# LM317-LM337.net
KiCad netlist of a schematic drawn in Altium Designer
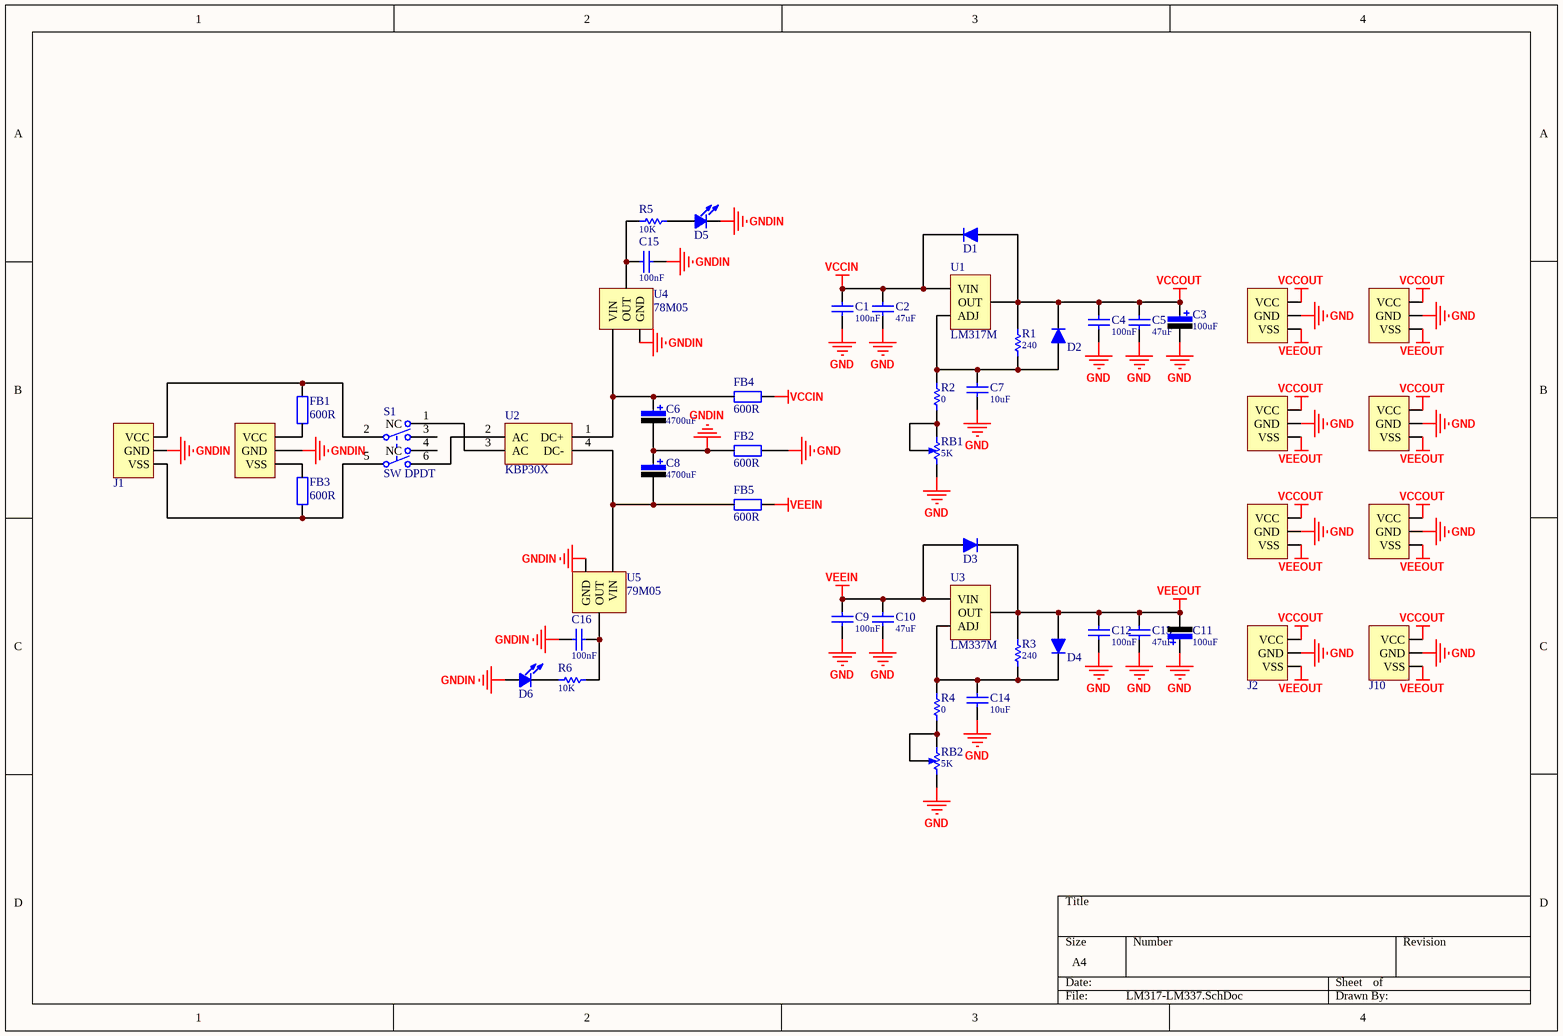
[diagram p0: LM317-LM337.SchDoc]

(export (version "E")
  (design (tool "Eeschema 10.0.6"))
  (components
    (comp (ref "C1")
      (value "100nF")
      (footprint "C0603-L")
      (description "贴片瓷片电容")
      (fields (field (name "Comment") "Cap-S"))
      (libsource (lib "CommonUsed") (part "Cap-S"))
    )
    (comp (ref "C2")
      (value "47uF")
      (footprint "C0805-L")
      (description "贴片瓷片电容")
      (fields (field (name "Comment") "Cap-S"))
      (libsource (lib "CommonUsed") (part "Cap-S"))
    )
    (comp (ref "C3")
      (value "100uF")
      (footprint "C-DIP-10")
      (description "极性直插电解电容")
      (fields (field (name "Comment") "C"))
      (libsource (lib "CommonUsed") (part "Cap-Pol-ER"))
    )
    (comp (ref "C4")
      (value "100nF")
      (footprint "C0603-L")
      (description "贴片瓷片电容")
      (fields (field (name "Comment") "Cap-S"))
      (libsource (lib "CommonUsed") (part "Cap-S"))
    )
    (comp (ref "C5")
      (value "47uF")
      (footprint "C0805-L")
      (description "贴片瓷片电容")
      (fields (field (name "Comment") "Cap-S"))
      (libsource (lib "CommonUsed") (part "Cap-S"))
    )
    (comp (ref "C6")
      (value "4700uF")
      (footprint "C-DIP-20")
      (description "极性直插电解电容")
      (fields (field (name "Comment") "C"))
      (libsource (lib "CommonUsed") (part "Cap-Pol-ER"))
    )
    (comp (ref "C7")
      (value "10uF")
      (footprint "C0603-L")
      (description "贴片瓷片电容")
      (fields (field (name "Comment") "Cap-S"))
      (libsource (lib "CommonUsed") (part "Cap-S"))
    )
    (comp (ref "C8")
      (value "4700uF")
      (footprint "C-DIP-20")
      (description "极性直插电解电容")
      (fields (field (name "Comment") "C"))
      (libsource (lib "CommonUsed") (part "Cap-Pol-ER"))
    )
    (comp (ref "C9")
      (value "100nF")
      (footprint "C0603-L")
      (description "贴片瓷片电容")
      (fields (field (name "Comment") "Cap-S"))
      (libsource (lib "CommonUsed") (part "Cap-S"))
    )
    (comp (ref "C10")
      (value "47uF")
      (footprint "C0805-L")
      (description "贴片瓷片电容")
      (fields (field (name "Comment") "Cap-S"))
      (libsource (lib "CommonUsed") (part "Cap-S"))
    )
    (comp (ref "C11")
      (value "100uF")
      (footprint "C-DIP-10")
      (description "极性直插电解电容")
      (fields (field (name "Comment") "C"))
      (libsource (lib "") (part "Cap-Pol-ER_1"))
    )
    (comp (ref "C12")
      (value "100nF")
      (footprint "C0603-L")
      (description "贴片瓷片电容")
      (fields (field (name "Comment") "Cap-S"))
      (libsource (lib "CommonUsed") (part "Cap-S"))
    )
    (comp (ref "C13")
      (value "47uF")
      (footprint "C0805-L")
      (description "贴片瓷片电容")
      (fields (field (name "Comment") "Cap-S"))
      (libsource (lib "CommonUsed") (part "Cap-S"))
    )
    (comp (ref "C14")
      (value "10uF")
      (footprint "C0603-L")
      (description "贴片瓷片电容")
      (fields (field (name "Comment") "Cap-S"))
      (libsource (lib "CommonUsed") (part "Cap-S"))
    )
    (comp (ref "C15")
      (value "100nF")
      (footprint "C0603-L")
      (description "贴片瓷片电容")
      (fields (field (name "Comment") "Cap-S"))
      (libsource (lib "CommonUsed") (part "Cap-S"))
    )
    (comp (ref "C16")
      (value "100nF")
      (footprint "C0603-L")
      (description "贴片瓷片电容")
      (fields (field (name "Comment") "Cap-S"))
      (libsource (lib "CommonUsed") (part "Cap-S"))
    )
    (comp (ref "D1")
      (value "D")
      (footprint "D-SMA")
      (description "二极管")
      (libsource (lib "CommonUsed") (part "Diode"))
    )
    (comp (ref "D2")
      (value "D")
      (footprint "D-SMA")
      (description "二极管")
      (libsource (lib "CommonUsed") (part "Diode"))
    )
    (comp (ref "D3")
      (value "D")
      (footprint "D-SMA")
      (description "二极管")
      (libsource (lib "CommonUsed") (part "Diode"))
    )
    (comp (ref "D4")
      (value "D")
      (footprint "D-SMA")
      (description "二极管")
      (libsource (lib "CommonUsed") (part "Diode"))
    )
    (comp (ref "D5")
      (value "LED")
      (footprint "Led-0805_L")
      (description "发光二极管")
      (libsource (lib "CommonUsed") (part "LED"))
    )
    (comp (ref "D6")
      (value "LED")
      (footprint "Led-0805_L")
      (description "发光二极管")
      (libsource (lib "CommonUsed") (part "LED"))
    )
    (comp (ref "FB1") (value "600R") (footprint "FB-0805") (libsource (lib "CommonUsed") (part "FB")))
    (comp (ref "FB2") (value "600R") (footprint "FB-0805") (libsource (lib "CommonUsed") (part "FB")))
    (comp (ref "FB3") (value "600R") (footprint "FB-0805") (libsource (lib "CommonUsed") (part "FB")))
    (comp (ref "FB4") (value "600R") (footprint "FB-0805") (libsource (lib "CommonUsed") (part "FB")))
    (comp (ref "FB5") (value "600R") (footprint "FB-0805") (libsource (lib "CommonUsed") (part "FB")))
    (comp (ref "J1") (value "接线座-3P") (footprint "KF128-5.08-3P") (libsource (lib "xz_C") (part "接线座-3P")))
    (comp (ref "J2") (value "接线座-3P") (footprint "KF128-5.08-3P") (libsource (lib "xz_C") (part "接线座-3P")))
    (comp (ref "J3")
      (value "Power-3P")
      (footprint "SIPA03")
      (description "供电端子")
      (libsource (lib "xz_C") (part "Power-3P"))
    )
    (comp (ref "J4")
      (value "Power-3P")
      (footprint "SIPA03")
      (description "供电端子")
      (libsource (lib "xz_C") (part "Power-3P"))
    )
    (comp (ref "J5")
      (value "Power-3P")
      (footprint "SIPA03")
      (description "供电端子")
      (libsource (lib "xz_C") (part "Power-3P"))
    )
    (comp (ref "J6")
      (value "Power-3P")
      (footprint "SIPA03")
      (description "供电端子")
      (libsource (lib "xz_C") (part "Power-3P"))
    )
    (comp (ref "J7")
      (value "Power-3P")
      (footprint "SIPA03")
      (description "供电端子")
      (libsource (lib "xz_C") (part "Power-3P"))
    )
    (comp (ref "J8")
      (value "Power-3P")
      (footprint "SIPA03")
      (description "供电端子")
      (libsource (lib "xz_C") (part "Power-3P"))
    )
    (comp (ref "J9")
      (value "Power-3P")
      (footprint "SIPA03")
      (description "供电端子")
      (libsource (lib "xz_C") (part "Power-3P"))
    )
    (comp (ref "J10") (value "接线座-3P") (footprint "KF128-5.08-3P") (libsource (lib "xz_C") (part "接线座-3P")))
    (comp (ref "R1")
      (value "240")
      (footprint "R0603-L")
      (description "贴片电阻")
      (fields (field (name "Comment") "R"))
      (libsource (lib "CommonUsed") (part "Res"))
    )
    (comp (ref "R2")
      (value "0")
      (footprint "R0603-L")
      (description "贴片电阻")
      (fields (field (name "Comment") "R"))
      (libsource (lib "CommonUsed") (part "Res"))
    )
    (comp (ref "R3")
      (value "240")
      (footprint "R0603-L")
      (description "贴片电阻")
      (fields (field (name "Comment") "R"))
      (libsource (lib "CommonUsed") (part "Res"))
    )
    (comp (ref "R4")
      (value "0")
      (footprint "R0603-L")
      (description "贴片电阻")
      (fields (field (name "Comment") "R"))
      (libsource (lib "CommonUsed") (part "Res"))
    )
    (comp (ref "R5")
      (value "10K")
      (footprint "R0603-L")
      (description "贴片电阻")
      (fields (field (name "Comment") "R"))
      (libsource (lib "xz_D") (part "Res"))
    )
    (comp (ref "R6")
      (value "10K")
      (footprint "R0603-L")
      (description "贴片电阻")
      (fields (field (name "Comment") "R"))
      (libsource (lib "xz_D") (part "Res"))
    )
    (comp (ref "RB1")
      (value "5K")
      (footprint "R_VR-3296W")
      (description "可调电阻")
      (fields (field (name "Comment") "R"))
      (libsource (lib "CommonUsed") (part "Res_Val"))
    )
    (comp (ref "RB2")
      (value "5K")
      (footprint "R_VR-3296W")
      (description "可调电阻")
      (fields (field (name "Comment") "R"))
      (libsource (lib "CommonUsed") (part "Res_Val"))
    )
    (comp (ref "S1")
      (value "SW DPDT")
      (footprint "SW_DPDT")
      (description "自锁开关")
      (fields (field (name "PUBLISHER") "Altium Limited"))
      (libsource (lib "CommonUsed") (part "SW DPDT"))
    )
    (comp (ref "U1") (value "LM317M") (footprint "TO-263-2") (libsource (lib "CommonUsed") (part "LM317M")))
    (comp (ref "U2") (value "KBP30X") (footprint "Bridge") (libsource (lib "CommonUsed") (part "Bridge")))
    (comp (ref "U3") (value "LM337M") (footprint "TO-263-2") (libsource (lib "CommonUsed") (part "LM337M")))
    (comp (ref "U4") (value "78M05") (footprint "TO-252") (libsource (lib "CommonUsed") (part "78M05")))
    (comp (ref "U5") (value "79M05") (footprint "TO-252") (libsource (lib "CommonUsed") (part "79M05")))
  )
  (nets
    (net (code "1") (name "GND") (class "Default")
      (node (ref "C1") (pin "1") (pinfunction "1_1") (pintype "passive"))
      (node (ref "C10") (pin "1") (pinfunction "1_1") (pintype "passive"))
      (node (ref "C11") (pin "1") (pinfunction "1_1") (pintype "passive"))
      (node (ref "C12") (pin "1") (pinfunction "1_1") (pintype "passive"))
      (node (ref "C13") (pin "1") (pinfunction "1_1") (pintype "passive"))
      (node (ref "C14") (pin "1") (pinfunction "1_1") (pintype "passive"))
      (node (ref "C2") (pin "1") (pinfunction "1_1") (pintype "passive"))
      (node (ref "C3") (pin "2") (pinfunction "2_2") (pintype "passive"))
      (node (ref "C4") (pin "1") (pinfunction "1_1") (pintype "passive"))
      (node (ref "C5") (pin "1") (pinfunction "1_1") (pintype "passive"))
      (node (ref "C7") (pin "1") (pinfunction "1_1") (pintype "passive"))
      (node (ref "C9") (pin "1") (pinfunction "1_1") (pintype "passive"))
      (node (ref "FB2") (pin "2") (pinfunction "2_2") (pintype "passive"))
      (node (ref "J10") (pin "2") (pinfunction "GND_2") (pintype "passive"))
      (node (ref "J2") (pin "2") (pinfunction "GND_2") (pintype "passive"))
      (node (ref "J4") (pin "2") (pinfunction "GND_2") (pintype "passive"))
      (node (ref "J5") (pin "2") (pinfunction "GND_2") (pintype "passive"))
      (node (ref "J6") (pin "2") (pinfunction "GND_2") (pintype "passive"))
      (node (ref "J7") (pin "2") (pinfunction "GND_2") (pintype "passive"))
      (node (ref "J8") (pin "2") (pinfunction "GND_2") (pintype "passive"))
      (node (ref "J9") (pin "2") (pinfunction "GND_2") (pintype "passive"))
      (node (ref "RB1") (pin "1") (pinfunction "1_1") (pintype "passive"))
      (node (ref "RB2") (pin "1") (pinfunction "1_1") (pintype "passive"))
    )
    (net (code "2") (name "GNDIN") (class "Default")
      (node (ref "C15") (pin "1") (pinfunction "1_1") (pintype "passive"))
      (node (ref "C16") (pin "1") (pinfunction "1_1") (pintype "passive"))
      (node (ref "C6") (pin "2") (pinfunction "2_2") (pintype "passive"))
      (node (ref "C8") (pin "1") (pinfunction "1_1") (pintype "passive"))
      (node (ref "D5") (pin "2") (pinfunction "2_2") (pintype "passive"))
      (node (ref "D6") (pin "1") (pinfunction "1_1") (pintype "passive"))
      (node (ref "FB2") (pin "1") (pinfunction "1_1") (pintype "passive"))
      (node (ref "J1") (pin "2") (pinfunction "GND_2") (pintype "passive"))
      (node (ref "J3") (pin "2") (pinfunction "GND_2") (pintype "passive"))
      (node (ref "U4") (pin "2") (pinfunction "GND_2") (pintype "passive"))
      (node (ref "U5") (pin "1") (pinfunction "GND_1") (pintype "passive"))
    )
    (net (code "3") (name "Net-(D5-Pad1)") (class "Default")
      (node (ref "D5") (pin "1") (pinfunction "1_1") (pintype "passive"))
      (node (ref "R5") (pin "2") (pinfunction "2_2") (pintype "passive"))
    )
    (net (code "4") (name "Net-(D6-Pad2)") (class "Default")
      (node (ref "D6") (pin "2") (pinfunction "2_2") (pintype "passive"))
      (node (ref "R6") (pin "1") (pinfunction "1_1") (pintype "passive"))
    )
    (net (code "5") (name "Net-(J1-VCC)") (class "Default")
      (node (ref "FB1") (pin "2") (pinfunction "2_2") (pintype "passive"))
      (node (ref "J1") (pin "1") (pinfunction "VCC_1") (pintype "passive"))
      (node (ref "S1") (pin "2") (pinfunction "1_2") (pintype "passive"))
    )
    (net (code "6") (name "Net-(J1-VSS)") (class "Default")
      (node (ref "FB3") (pin "2") (pinfunction "2_2") (pintype "passive"))
      (node (ref "J1") (pin "3") (pinfunction "VSS_3") (pintype "passive"))
      (node (ref "S1") (pin "5") (pinfunction "COMMON2_5") (pintype "passive"))
    )
    (net (code "7") (name "Net-(J3-VCC)") (class "Default")
      (node (ref "FB1") (pin "1") (pinfunction "1_1") (pintype "passive"))
      (node (ref "J3") (pin "1") (pinfunction "VCC_1") (pintype "passive"))
    )
    (net (code "8") (name "Net-(J3-VSS)") (class "Default")
      (node (ref "FB3") (pin "1") (pinfunction "1_1") (pintype "passive"))
      (node (ref "J3") (pin "3") (pinfunction "VSS_3") (pintype "passive"))
    )
    (net (code "9") (name "Net-(R2-Pad2)") (class "Default")
      (node (ref "R2") (pin "2") (pinfunction "2_2") (pintype "passive"))
      (node (ref "RB1") (pin "2") (pinfunction "2_2") (pintype "passive"))
      (node (ref "RB1") (pin "3") (pinfunction "3_3") (pintype "passive"))
    )
    (net (code "10") (name "Net-(R4-Pad2)") (class "Default")
      (node (ref "R4") (pin "2") (pinfunction "2_2") (pintype "passive"))
      (node (ref "RB2") (pin "2") (pinfunction "2_2") (pintype "passive"))
      (node (ref "RB2") (pin "3") (pinfunction "3_3") (pintype "passive"))
    )
    (net (code "11") (name "Net-(S1-NC-Pad1)") (class "Default")
      (node (ref "S1") (pin "1") (pinfunction "NC_1") (pintype "passive"))
      (node (ref "U2") (pin "3") (pinfunction "AC_3") (pintype "passive"))
    )
    (net (code "12") (name "Net-(S1-NO2)") (class "Default")
      (node (ref "S1") (pin "6") (pinfunction "NO2_6") (pintype "passive"))
      (node (ref "U2") (pin "2") (pinfunction "AC_2") (pintype "passive"))
    )
    (net (code "13") (name "Net-(U1-ADJ)") (class "Default")
      (node (ref "C7") (pin "2") (pinfunction "2_2") (pintype "passive"))
      (node (ref "D2") (pin "1") (pinfunction "1_1") (pintype "passive"))
      (node (ref "R1") (pin "2") (pinfunction "2_2") (pintype "passive"))
      (node (ref "R2") (pin "1") (pinfunction "1_1") (pintype "passive"))
      (node (ref "U1") (pin "1") (pinfunction "ADJ_1") (pintype "passive"))
    )
    (net (code "14") (name "Net-(U2-DC+)") (class "Default")
      (node (ref "C6") (pin "1") (pinfunction "1_1") (pintype "passive"))
      (node (ref "FB4") (pin "1") (pinfunction "1_1") (pintype "passive"))
      (node (ref "U2") (pin "1") (pinfunction "DC+_1") (pintype "passive"))
      (node (ref "U4") (pin "1") (pinfunction "VIN_1") (pintype "passive"))
    )
    (net (code "15") (name "Net-(U2-DC-)") (class "Default")
      (node (ref "C8") (pin "2") (pinfunction "2_2") (pintype "passive"))
      (node (ref "FB5") (pin "1") (pinfunction "1_1") (pintype "passive"))
      (node (ref "U2") (pin "4") (pinfunction "DC-_4") (pintype "passive"))
      (node (ref "U5") (pin "2") (pinfunction "VIN_2") (pintype "passive"))
    )
    (net (code "16") (name "Net-(U3-ADJ)") (class "Default")
      (node (ref "C14") (pin "2") (pinfunction "2_2") (pintype "passive"))
      (node (ref "D4") (pin "2") (pinfunction "2_2") (pintype "passive"))
      (node (ref "R3") (pin "2") (pinfunction "2_2") (pintype "passive"))
      (node (ref "R4") (pin "1") (pinfunction "1_1") (pintype "passive"))
      (node (ref "U3") (pin "1") (pinfunction "ADJ_1") (pintype "passive"))
    )
    (net (code "17") (name "Net-(U4-OUT)") (class "Default")
      (node (ref "C15") (pin "2") (pinfunction "2_2") (pintype "passive"))
      (node (ref "R5") (pin "1") (pinfunction "1_1") (pintype "passive"))
      (node (ref "U4") (pin "3") (pinfunction "OUT_3") (pintype "passive"))
    )
    (net (code "18") (name "Net-(U5-OUT)") (class "Default")
      (node (ref "C16") (pin "2") (pinfunction "2_2") (pintype "passive"))
      (node (ref "R6") (pin "2") (pinfunction "2_2") (pintype "passive"))
      (node (ref "U5") (pin "3") (pinfunction "OUT_3") (pintype "passive"))
    )
    (net (code "19") (name "VCCIN") (class "Default")
      (node (ref "C1") (pin "2") (pinfunction "2_2") (pintype "passive"))
      (node (ref "C2") (pin "2") (pinfunction "2_2") (pintype "passive"))
      (node (ref "D1") (pin "2") (pinfunction "2_2") (pintype "passive"))
      (node (ref "FB4") (pin "2") (pinfunction "2_2") (pintype "passive"))
      (node (ref "U1") (pin "3") (pinfunction "VIN_3") (pintype "passive"))
    )
    (net (code "20") (name "VCCOUT") (class "Default")
      (node (ref "C3") (pin "1") (pinfunction "1_1") (pintype "passive"))
      (node (ref "C4") (pin "2") (pinfunction "2_2") (pintype "passive"))
      (node (ref "C5") (pin "2") (pinfunction "2_2") (pintype "passive"))
      (node (ref "D1") (pin "1") (pinfunction "1_1") (pintype "passive"))
      (node (ref "D2") (pin "2") (pinfunction "2_2") (pintype "passive"))
      (node (ref "J10") (pin "1") (pinfunction "VCC_1") (pintype "passive"))
      (node (ref "J2") (pin "1") (pinfunction "VCC_1") (pintype "passive"))
      (node (ref "J4") (pin "1") (pinfunction "VCC_1") (pintype "passive"))
      (node (ref "J5") (pin "1") (pinfunction "VCC_1") (pintype "passive"))
      (node (ref "J6") (pin "1") (pinfunction "VCC_1") (pintype "passive"))
      (node (ref "J7") (pin "1") (pinfunction "VCC_1") (pintype "passive"))
      (node (ref "J8") (pin "1") (pinfunction "VCC_1") (pintype "passive"))
      (node (ref "J9") (pin "1") (pinfunction "VCC_1") (pintype "passive"))
      (node (ref "R1") (pin "1") (pinfunction "1_1") (pintype "passive"))
      (node (ref "U1") (pin "2") (pinfunction "OUT_2") (pintype "passive"))
    )
    (net (code "21") (name "VEEIN") (class "Default")
      (node (ref "C10") (pin "2") (pinfunction "2_2") (pintype "passive"))
      (node (ref "C9") (pin "2") (pinfunction "2_2") (pintype "passive"))
      (node (ref "D3") (pin "1") (pinfunction "1_1") (pintype "passive"))
      (node (ref "FB5") (pin "2") (pinfunction "2_2") (pintype "passive"))
      (node (ref "U3") (pin "2") (pinfunction "VIN_2") (pintype "passive"))
    )
    (net (code "22") (name "VEEOUT") (class "Default")
      (node (ref "C11") (pin "2") (pinfunction "2_2") (pintype "passive"))
      (node (ref "C12") (pin "2") (pinfunction "2_2") (pintype "passive"))
      (node (ref "C13") (pin "2") (pinfunction "2_2") (pintype "passive"))
      (node (ref "D3") (pin "2") (pinfunction "2_2") (pintype "passive"))
      (node (ref "D4") (pin "1") (pinfunction "1_1") (pintype "passive"))
      (node (ref "J10") (pin "3") (pinfunction "VSS_3") (pintype "passive"))
      (node (ref "J2") (pin "3") (pinfunction "VSS_3") (pintype "passive"))
      (node (ref "J4") (pin "3") (pinfunction "VSS_3") (pintype "passive"))
      (node (ref "J5") (pin "3") (pinfunction "VSS_3") (pintype "passive"))
      (node (ref "J6") (pin "3") (pinfunction "VSS_3") (pintype "passive"))
      (node (ref "J7") (pin "3") (pinfunction "VSS_3") (pintype "passive"))
      (node (ref "J8") (pin "3") (pinfunction "VSS_3") (pintype "passive"))
      (node (ref "J9") (pin "3") (pinfunction "VSS_3") (pintype "passive"))
      (node (ref "R3") (pin "1") (pinfunction "1_1") (pintype "passive"))
      (node (ref "U3") (pin "3") (pinfunction "OUT_3") (pintype "passive"))
    )
    (net (code "23") (name "unconnected-(S1-NC-Pad4)") (class "Default")
      (node (ref "S1") (pin "4") (pinfunction "NC_4") (pintype "passive"))
    )
    (net (code "24") (name "unconnected-(S1-NO1-Pad3)") (class "Default")
      (node (ref "S1") (pin "3") (pinfunction "NO1_3") (pintype "passive"))
    )
  )
)
